# RGB_Sencer.net
KiCad netlist of a schematic drawn in Altium Designer
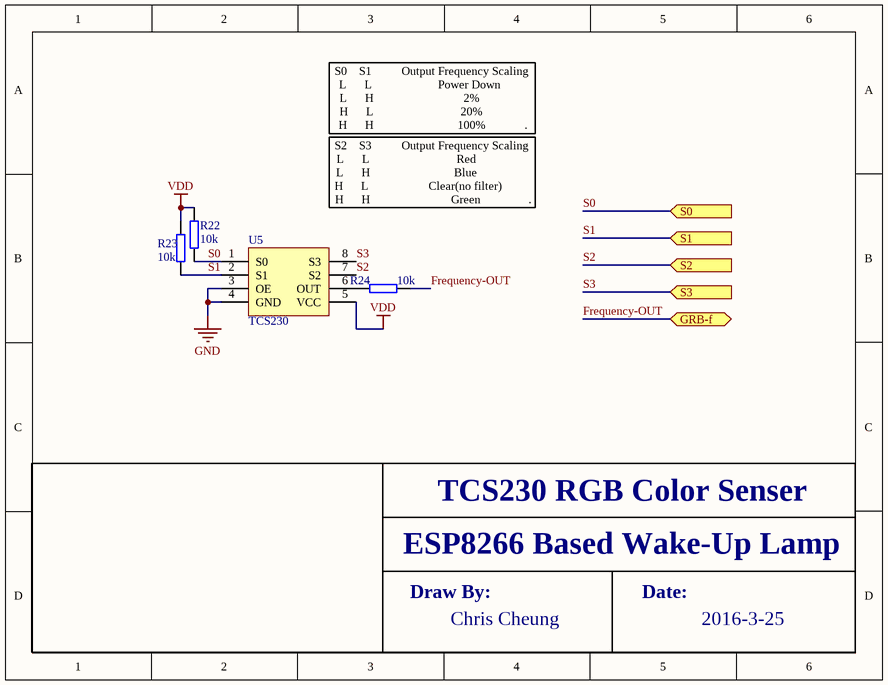
[diagram p0: RGB Sencer.SchDoc]

(export (version "E")
  (design (tool "Eeschema 10.0.6"))
  (components
    (comp (ref "R22")
      (value "10k")
      (footprint "SMT_R_0402")
      (description "Surface mount resistor 0402")
      (libsource (lib "Vowstar_Basic_Device") (part "SMT_R_0402"))
    )
    (comp (ref "R23")
      (value "10k")
      (footprint "SMT_R_0402")
      (description "Surface mount resistor 0402")
      (libsource (lib "Vowstar_Basic_Device") (part "SMT_R_0402"))
    )
    (comp (ref "R24")
      (value "10k")
      (footprint "SMT_R_0402")
      (description "Surface mount resistor 0402")
      (libsource (lib "Vowstar_Basic_Device") (part "SMT_R_0402"))
    )
    (comp (ref "U5")
      (value "TCS230")
      (footprint "SO-8")
      (description "Color sensor")
      (libsource (lib "Schlib1") (part "TCS230"))
    )
  )
  (nets
    (net (code "1") (name "/Frequency-OUT") (class "Default")
      (node (ref "R24") (pin "2") (pinfunction "2_2") (pintype "passive"))
    )
    (net (code "2") (name "/S0") (class "Default")
      (node (ref "R22") (pin "1") (pinfunction "1_1") (pintype "passive"))
      (node (ref "U5") (pin "1") (pinfunction "S0_1") (pintype "passive"))
    )
    (net (code "3") (name "/S1") (class "Default")
      (node (ref "R23") (pin "1") (pinfunction "1_1") (pintype "passive"))
      (node (ref "U5") (pin "2") (pinfunction "S1_2") (pintype "passive"))
    )
    (net (code "4") (name "/S2") (class "Default")
      (node (ref "U5") (pin "7") (pinfunction "S2_7") (pintype "passive"))
    )
    (net (code "5") (name "/S3") (class "Default")
      (node (ref "U5") (pin "8") (pinfunction "S3_8") (pintype "passive"))
    )
    (net (code "6") (name "GND") (class "Default")
      (node (ref "U5") (pin "3") (pinfunction "OE_3") (pintype "passive"))
      (node (ref "U5") (pin "4") (pinfunction "GND_4") (pintype "passive"))
    )
    (net (code "7") (name "Net-(U5-OUT)") (class "Default")
      (node (ref "R24") (pin "1") (pinfunction "1_1") (pintype "passive"))
      (node (ref "U5") (pin "6") (pinfunction "OUT_6") (pintype "passive"))
    )
    (net (code "8") (name "VDD") (class "Default")
      (node (ref "R22") (pin "2") (pinfunction "2_2") (pintype "passive"))
      (node (ref "R23") (pin "2") (pinfunction "2_2") (pintype "passive"))
      (node (ref "U5") (pin "5") (pinfunction "VCC_5") (pintype "passive"))
    )
  )
)
